# payload-externalPCB-version2-modif2.net
KiCad netlist of a schematic drawn in EAGLE
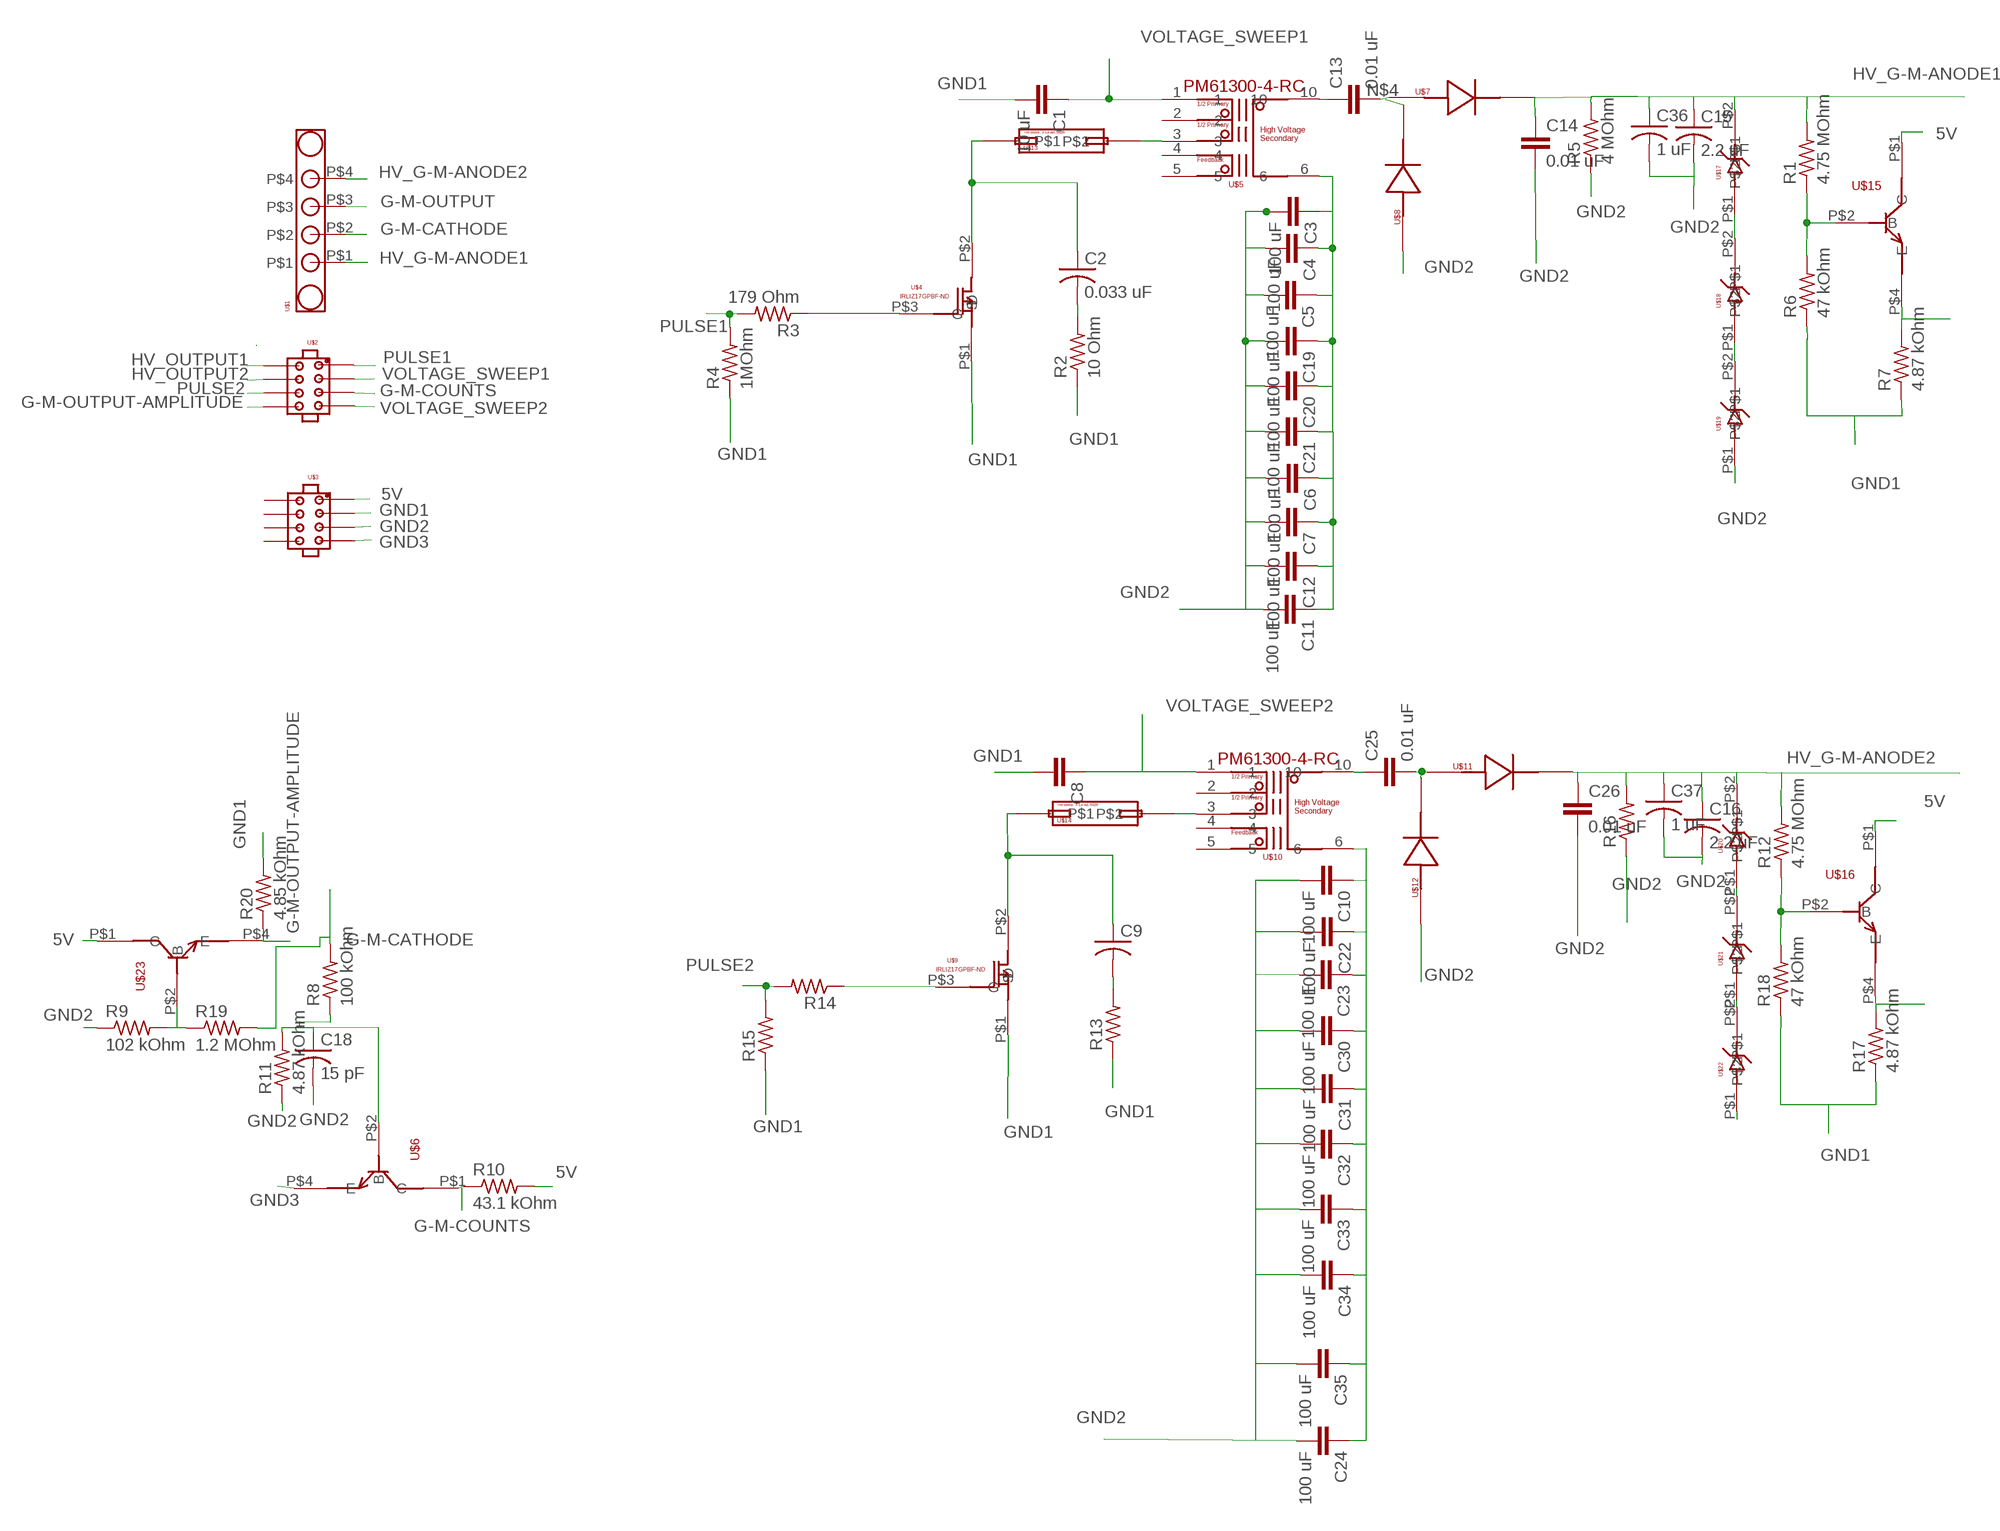
[diagram p0: schematic, sheet 1]

(export (version "E")
  (design (tool "Eeschema 10.0.6"))
  (components
    (comp (ref "C1")
      (value "10 uF")
      (footprint "eagle-import:C1210")
      (libsource (lib "eagle-import") (part "C-EUC1210"))
    )
    (comp (ref "C2")
      (value "0.033 uF")
      (footprint "eagle-import:C0805")
      (libsource (lib "eagle-import") (part "C-USC0805"))
    )
    (comp (ref "C3")
      (value "100 uF")
      (footprint "eagle-import:C1210")
      (libsource (lib "eagle-import") (part "C-EUC1210"))
    )
    (comp (ref "C4")
      (value "100 uF")
      (footprint "eagle-import:C1210")
      (libsource (lib "eagle-import") (part "C-EUC1210"))
    )
    (comp (ref "C5")
      (value "100 uF")
      (footprint "eagle-import:C1210")
      (libsource (lib "eagle-import") (part "C-EUC1210"))
    )
    (comp (ref "C6")
      (value "100 uF")
      (footprint "eagle-import:C1210")
      (libsource (lib "eagle-import") (part "C-EUC1210"))
    )
    (comp (ref "C7")
      (value "100 uF")
      (footprint "eagle-import:C1210")
      (libsource (lib "eagle-import") (part "C-EUC1210"))
    )
    (comp (ref "C8")
      (value "C-EUC1210")
      (footprint "eagle-import:C1210")
      (libsource (lib "eagle-import") (part "C-EUC1210"))
    )
    (comp (ref "C9")
      (value "C-USC0805")
      (footprint "eagle-import:C0805")
      (libsource (lib "eagle-import") (part "C-USC0805"))
    )
    (comp (ref "C10")
      (value "100 uF")
      (footprint "eagle-import:C1210")
      (libsource (lib "eagle-import") (part "C-EUC1210"))
    )
    (comp (ref "C11")
      (value "100 uF")
      (footprint "eagle-import:C1210")
      (libsource (lib "eagle-import") (part "C-EUC1210"))
    )
    (comp (ref "C12")
      (value "100 uF")
      (footprint "eagle-import:C1210")
      (libsource (lib "eagle-import") (part "C-EUC1210"))
    )
    (comp (ref "C13")
      (value "0.01 uF")
      (footprint "eagle-import:C1206")
      (libsource (lib "eagle-import") (part "C-EUC1206"))
    )
    (comp (ref "C14")
      (value "0.01 uF")
      (footprint "eagle-import:C1206")
      (libsource (lib "eagle-import") (part "C-EUC1206"))
    )
    (comp (ref "C15")
      (value "2.2 uF")
      (footprint "eagle-import:C2220K")
      (libsource (lib "eagle-import") (part "C-USC2220K"))
    )
    (comp (ref "C16")
      (value "2.2 uF")
      (footprint "eagle-import:C2220K")
      (libsource (lib "eagle-import") (part "C-USC2220K"))
    )
    (comp (ref "C18")
      (value "15 pF")
      (footprint "eagle-import:C0805")
      (libsource (lib "eagle-import") (part "C-USC0805"))
    )
    (comp (ref "C19")
      (value "100 uF")
      (footprint "eagle-import:C1210")
      (libsource (lib "eagle-import") (part "C-EUC1210"))
    )
    (comp (ref "C20")
      (value "100 uF")
      (footprint "eagle-import:C1210")
      (libsource (lib "eagle-import") (part "C-EUC1210"))
    )
    (comp (ref "C21")
      (value "100 uF")
      (footprint "eagle-import:C1210")
      (libsource (lib "eagle-import") (part "C-EUC1210"))
    )
    (comp (ref "C22")
      (value "100 uF")
      (footprint "eagle-import:C1210")
      (libsource (lib "eagle-import") (part "C-EUC1210"))
    )
    (comp (ref "C23")
      (value "100 uF")
      (footprint "eagle-import:C1210")
      (libsource (lib "eagle-import") (part "C-EUC1210"))
    )
    (comp (ref "C24")
      (value "100 uF")
      (footprint "eagle-import:C1210")
      (libsource (lib "eagle-import") (part "C-EUC1210"))
    )
    (comp (ref "C25")
      (value "0.01 uF")
      (footprint "eagle-import:C1206")
      (libsource (lib "eagle-import") (part "C-EUC1206"))
    )
    (comp (ref "C26")
      (value "0.01 uF")
      (footprint "eagle-import:C1206")
      (libsource (lib "eagle-import") (part "C-EUC1206"))
    )
    (comp (ref "C30")
      (value "100 uF")
      (footprint "eagle-import:C1210")
      (libsource (lib "eagle-import") (part "C-EUC1210"))
    )
    (comp (ref "C31")
      (value "100 uF")
      (footprint "eagle-import:C1210")
      (libsource (lib "eagle-import") (part "C-EUC1210"))
    )
    (comp (ref "C32")
      (value "100 uF")
      (footprint "eagle-import:C1210")
      (libsource (lib "eagle-import") (part "C-EUC1210"))
    )
    (comp (ref "C33")
      (value "100 uF")
      (footprint "eagle-import:C1210")
      (libsource (lib "eagle-import") (part "C-EUC1210"))
    )
    (comp (ref "C34")
      (value "100 uF")
      (footprint "eagle-import:C1210")
      (libsource (lib "eagle-import") (part "C-EUC1210"))
    )
    (comp (ref "C35")
      (value "100 uF")
      (footprint "eagle-import:C1210")
      (libsource (lib "eagle-import") (part "C-EUC1210"))
    )
    (comp (ref "C36")
      (value "1 uF")
      (footprint "eagle-import:C2220K")
      (libsource (lib "eagle-import") (part "C-USC2220K"))
    )
    (comp (ref "C37")
      (value "1 uF")
      (footprint "eagle-import:C2220K")
      (libsource (lib "eagle-import") (part "C-USC2220K"))
    )
    (comp (ref "R1")
      (value "4.75 MOhm")
      (footprint "eagle-import:R1206")
      (libsource (lib "eagle-import") (part "R-US_R1206"))
    )
    (comp (ref "R2")
      (value "10 Ohm")
      (footprint "eagle-import:R2010")
      (libsource (lib "eagle-import") (part "R-US_R2010"))
    )
    (comp (ref "R3")
      (value "179 Ohm")
      (footprint "eagle-import:R2010")
      (libsource (lib "eagle-import") (part "R-US_R2010"))
    )
    (comp (ref "R4")
      (value "1MOhm")
      (footprint "eagle-import:R2010")
      (libsource (lib "eagle-import") (part "R-US_R2010"))
    )
    (comp (ref "R5")
      (value "4 MOhm")
      (footprint "eagle-import:R2010")
      (libsource (lib "eagle-import") (part "R-US_R2010"))
    )
    (comp (ref "R6")
      (value "47 kOhm")
      (footprint "eagle-import:R1210")
      (libsource (lib "eagle-import") (part "R-US_R1210"))
    )
    (comp (ref "R7")
      (value "4.87 kOhm")
      (footprint "eagle-import:R2010")
      (libsource (lib "eagle-import") (part "R-US_R2010"))
    )
    (comp (ref "R8")
      (value "100 kOhm")
      (footprint "eagle-import:R2010")
      (libsource (lib "eagle-import") (part "R-US_R2010"))
    )
    (comp (ref "R9")
      (value "102 kOhm")
      (footprint "eagle-import:R1206")
      (libsource (lib "eagle-import") (part "R-US_R1206"))
    )
    (comp (ref "R10")
      (value "43.1 kOhm")
      (footprint "eagle-import:R2010")
      (libsource (lib "eagle-import") (part "R-US_R2010"))
    )
    (comp (ref "R11")
      (value "4.87 kOhm")
      (footprint "eagle-import:R1210")
      (libsource (lib "eagle-import") (part "R-US_R1210"))
    )
    (comp (ref "R12")
      (value "4.75 MOhm")
      (footprint "eagle-import:R1206")
      (libsource (lib "eagle-import") (part "R-US_R1206"))
    )
    (comp (ref "R13")
      (value "R-US_R2010")
      (footprint "eagle-import:R2010")
      (libsource (lib "eagle-import") (part "R-US_R2010"))
    )
    (comp (ref "R14")
      (value "R-US_R2010")
      (footprint "eagle-import:R2010")
      (libsource (lib "eagle-import") (part "R-US_R2010"))
    )
    (comp (ref "R15")
      (value "R-US_R2010")
      (footprint "eagle-import:R2010")
      (libsource (lib "eagle-import") (part "R-US_R2010"))
    )
    (comp (ref "R16")
      (value "R-US_R2010")
      (footprint "eagle-import:R2010")
      (libsource (lib "eagle-import") (part "R-US_R2010"))
    )
    (comp (ref "R17")
      (value "4.87 kOhm")
      (footprint "eagle-import:R2010")
      (libsource (lib "eagle-import") (part "R-US_R2010"))
    )
    (comp (ref "R18")
      (value "47 kOhm")
      (footprint "eagle-import:R1210")
      (libsource (lib "eagle-import") (part "R-US_R1210"))
    )
    (comp (ref "R19")
      (value "1.2 MOhm")
      (footprint "eagle-import:R1206")
      (libsource (lib "eagle-import") (part "R-US_R1206"))
    )
    (comp (ref "R20")
      (value "4.85 kOhm")
      (footprint "eagle-import:R2010")
      (libsource (lib "eagle-import") (part "R-US_R2010"))
    )
    (comp (ref "U$1")
      (value "M80-5000000M2-04-331-00-000")
      (footprint "eagle-import:M80-5000000M2-04-331-00-000")
      (libsource (lib "eagle-import") (part "M80-5000000M2-04-331-00-000"))
    )
    (comp (ref "U$2")
      (value "M80-8670805")
      (footprint "eagle-import:M80-8670805")
      (libsource (lib "eagle-import") (part "M80-8670805"))
    )
    (comp (ref "U$3")
      (value "M80-8670805")
      (footprint "eagle-import:M80-8670805")
      (libsource (lib "eagle-import") (part "M80-8670805"))
    )
    (comp (ref "U$4")
      (value "IRLIZ14GPBF-ND-SCHEMATICS")
      (footprint "eagle-import:TO-220FULLPAK-IRLIZ14GPBF-ND")
      (libsource (lib "eagle-import") (part "IRLIZ14GPBF-ND-SCHEMATICS"))
    )
    (comp (ref "U$5")
      (value "PM61300-4-RC")
      (footprint "eagle-import:PM61300-4-RC")
      (libsource (lib "eagle-import") (part "PM61300-4-RC"))
    )
    (comp (ref "U$6")
      (value "PZT3904-SOT223-SCHEMATICS")
      (footprint "eagle-import:SOT223-PZT3904")
      (libsource (lib "eagle-import") (part "PZT3904-SOT223-SCHEMATICS"))
    )
    (comp (ref "U$7")
      (value "S1J-SCHEMATICS")
      (footprint "eagle-import:DO-214AC-S1J")
      (libsource (lib "eagle-import") (part "S1J-SCHEMATICS"))
    )
    (comp (ref "U$8")
      (value "S1J-SCHEMATICS")
      (footprint "eagle-import:DO-214AC-S1J")
      (libsource (lib "eagle-import") (part "S1J-SCHEMATICS"))
    )
    (comp (ref "U$9")
      (value "IRLIZ14GPBF-ND-SCHEMATICS")
      (footprint "eagle-import:TO-220FULLPAK-IRLIZ14GPBF-ND")
      (libsource (lib "eagle-import") (part "IRLIZ14GPBF-ND-SCHEMATICS"))
    )
    (comp (ref "U$10")
      (value "PM61300-4-RC")
      (footprint "eagle-import:PM61300-4-RC")
      (libsource (lib "eagle-import") (part "PM61300-4-RC"))
    )
    (comp (ref "U$11")
      (value "S1J-SCHEMATICS")
      (footprint "eagle-import:DO-214AC-S1J")
      (libsource (lib "eagle-import") (part "S1J-SCHEMATICS"))
    )
    (comp (ref "U$12")
      (value "S1J-SCHEMATICS")
      (footprint "eagle-import:DO-214AC-S1J")
      (libsource (lib "eagle-import") (part "S1J-SCHEMATICS"))
    )
    (comp (ref "U$13")
      (value "RESISTOR-J-LEAD-5W")
      (footprint "eagle-import:PACKAGE-13573-J-LEAD")
      (libsource (lib "eagle-import") (part "RESISTOR-J-LEAD-5W"))
    )
    (comp (ref "U$14")
      (value "RESISTOR-J-LEAD-5W")
      (footprint "eagle-import:PACKAGE-13573-J-LEAD")
      (libsource (lib "eagle-import") (part "RESISTOR-J-LEAD-5W"))
    )
    (comp (ref "U$15")
      (value "PZT3904-SOT223-SCHEMATICS")
      (footprint "eagle-import:SOT223-PZT3904")
      (libsource (lib "eagle-import") (part "PZT3904-SOT223-SCHEMATICS"))
    )
    (comp (ref "U$16")
      (value "PZT3904-SOT223-SCHEMATICS")
      (footprint "eagle-import:SOT223-PZT3904")
      (libsource (lib "eagle-import") (part "PZT3904-SOT223-SCHEMATICS"))
    )
    (comp (ref "U$17")
      (value "SMBJ5388B-ZENER-DIODE-200V")
      (footprint "eagle-import:DO-214AA-SMBJ5388B-ZENER")
      (libsource (lib "eagle-import") (part "SMBJ5388B-ZENER-DIODE-200V"))
    )
    (comp (ref "U$18")
      (value "SMBJ5388B-ZENER-DIODE-200V")
      (footprint "eagle-import:DO-214AA-SMBJ5388B-ZENER")
      (libsource (lib "eagle-import") (part "SMBJ5388B-ZENER-DIODE-200V"))
    )
    (comp (ref "U$19")
      (value "SMBJ5388B-ZENER-DIODE-200V")
      (footprint "eagle-import:DO-214AA-SMBJ5388B-ZENER")
      (libsource (lib "eagle-import") (part "SMBJ5388B-ZENER-DIODE-200V"))
    )
    (comp (ref "U$20")
      (value "SMBJ5388B-ZENER-DIODE-200V")
      (footprint "eagle-import:DO-214AA-SMBJ5388B-ZENER")
      (libsource (lib "eagle-import") (part "SMBJ5388B-ZENER-DIODE-200V"))
    )
    (comp (ref "U$21")
      (value "SMBJ5388B-ZENER-DIODE-200V")
      (footprint "eagle-import:DO-214AA-SMBJ5388B-ZENER")
      (libsource (lib "eagle-import") (part "SMBJ5388B-ZENER-DIODE-200V"))
    )
    (comp (ref "U$22")
      (value "SMBJ5388B-ZENER-DIODE-200V")
      (footprint "eagle-import:DO-214AA-SMBJ5388B-ZENER")
      (libsource (lib "eagle-import") (part "SMBJ5388B-ZENER-DIODE-200V"))
    )
    (comp (ref "U$23")
      (value "PZT3904-SOT223-SCHEMATICS")
      (footprint "eagle-import:SOT223-PZT3904")
      (libsource (lib "eagle-import") (part "PZT3904-SOT223-SCHEMATICS"))
    )
  )
  (nets
    (net (code "1") (name "/5V") (class "Default")
      (node (ref "R10") (pin "2") (pinfunction "2_2") (pintype "passive"))
      (node (ref "U$15") (pin "P$1") (pinfunction "C_P$1") (pintype "bidirectional"))
      (node (ref "U$16") (pin "P$1") (pinfunction "C_P$1") (pintype "bidirectional"))
      (node (ref "U$23") (pin "P$1") (pinfunction "C_P$1") (pintype "bidirectional"))
      (node (ref "U$3") (pin "P$1") (pinfunction "P$1_P$1") (pintype "bidirectional"))
    )
    (net (code "2") (name "/G-M-CATHODE") (class "Default")
      (node (ref "R19") (pin "2") (pinfunction "2_2") (pintype "passive"))
      (node (ref "R8") (pin "2") (pinfunction "2_2") (pintype "passive"))
      (node (ref "U$1") (pin "P$2") (pinfunction "P$2_P$2") (pintype "bidirectional"))
    )
    (net (code "3") (name "/G-M-COUNTS") (class "Default")
      (node (ref "R10") (pin "1") (pinfunction "1_1") (pintype "passive"))
      (node (ref "U$2") (pin "P$3") (pinfunction "P$3_P$3") (pintype "bidirectional"))
      (node (ref "U$6") (pin "P$1") (pinfunction "C_P$1") (pintype "bidirectional"))
    )
    (net (code "4") (name "/G-M-OUTPUT") (class "Default")
      (node (ref "U$1") (pin "P$3") (pinfunction "P$3_P$3") (pintype "bidirectional"))
    )
    (net (code "5") (name "/G-M-OUTPUT-AMPLITUDE") (class "Default")
      (node (ref "R20") (pin "1") (pinfunction "1_1") (pintype "passive"))
      (node (ref "U$2") (pin "P$8") (pinfunction "P$8_P$8") (pintype "bidirectional"))
      (node (ref "U$23") (pin "P$4") (pinfunction "E_P$4") (pintype "bidirectional"))
    )
    (net (code "6") (name "/GND1") (class "Default")
      (node (ref "C1") (pin "2") (pinfunction "2_2") (pintype "passive"))
      (node (ref "C8") (pin "2") (pinfunction "2_2") (pintype "passive"))
      (node (ref "R13") (pin "1") (pinfunction "1_1") (pintype "passive"))
      (node (ref "R15") (pin "1") (pinfunction "1_1") (pintype "passive"))
      (node (ref "R17") (pin "1") (pinfunction "1_1") (pintype "passive"))
      (node (ref "R18") (pin "1") (pinfunction "1_1") (pintype "passive"))
      (node (ref "R2") (pin "1") (pinfunction "1_1") (pintype "passive"))
      (node (ref "R20") (pin "2") (pinfunction "2_2") (pintype "passive"))
      (node (ref "R4") (pin "1") (pinfunction "1_1") (pintype "passive"))
      (node (ref "R6") (pin "1") (pinfunction "1_1") (pintype "passive"))
      (node (ref "R7") (pin "1") (pinfunction "1_1") (pintype "passive"))
      (node (ref "U$3") (pin "P$2") (pinfunction "P$2_P$2") (pintype "bidirectional"))
      (node (ref "U$4") (pin "P$1") (pinfunction "S_P$1") (pintype "bidirectional"))
      (node (ref "U$9") (pin "P$1") (pinfunction "S_P$1") (pintype "bidirectional"))
    )
    (net (code "7") (name "/GND2") (class "Default")
      (node (ref "C10") (pin "2") (pinfunction "2_2") (pintype "passive"))
      (node (ref "C11") (pin "2") (pinfunction "2_2") (pintype "passive"))
      (node (ref "C12") (pin "2") (pinfunction "2_2") (pintype "passive"))
      (node (ref "C14") (pin "2") (pinfunction "2_2") (pintype "passive"))
      (node (ref "C15") (pin "2") (pinfunction "2_2") (pintype "passive"))
      (node (ref "C16") (pin "2") (pinfunction "2_2") (pintype "passive"))
      (node (ref "C18") (pin "2") (pinfunction "2_2") (pintype "passive"))
      (node (ref "C19") (pin "2") (pinfunction "2_2") (pintype "passive"))
      (node (ref "C20") (pin "2") (pinfunction "2_2") (pintype "passive"))
      (node (ref "C21") (pin "2") (pinfunction "2_2") (pintype "passive"))
      (node (ref "C22") (pin "2") (pinfunction "2_2") (pintype "passive"))
      (node (ref "C23") (pin "2") (pinfunction "2_2") (pintype "passive"))
      (node (ref "C24") (pin "2") (pinfunction "2_2") (pintype "passive"))
      (node (ref "C26") (pin "2") (pinfunction "2_2") (pintype "passive"))
      (node (ref "C3") (pin "2") (pinfunction "2_2") (pintype "passive"))
      (node (ref "C30") (pin "2") (pinfunction "2_2") (pintype "passive"))
      (node (ref "C31") (pin "2") (pinfunction "2_2") (pintype "passive"))
      (node (ref "C32") (pin "2") (pinfunction "2_2") (pintype "passive"))
      (node (ref "C33") (pin "2") (pinfunction "2_2") (pintype "passive"))
      (node (ref "C34") (pin "2") (pinfunction "2_2") (pintype "passive"))
      (node (ref "C35") (pin "2") (pinfunction "2_2") (pintype "passive"))
      (node (ref "C36") (pin "2") (pinfunction "2_2") (pintype "passive"))
      (node (ref "C37") (pin "2") (pinfunction "2_2") (pintype "passive"))
      (node (ref "C4") (pin "2") (pinfunction "2_2") (pintype "passive"))
      (node (ref "C5") (pin "2") (pinfunction "2_2") (pintype "passive"))
      (node (ref "C6") (pin "2") (pinfunction "2_2") (pintype "passive"))
      (node (ref "C7") (pin "2") (pinfunction "2_2") (pintype "passive"))
      (node (ref "R11") (pin "1") (pinfunction "1_1") (pintype "passive"))
      (node (ref "R16") (pin "1") (pinfunction "1_1") (pintype "passive"))
      (node (ref "R5") (pin "1") (pinfunction "1_1") (pintype "passive"))
      (node (ref "R9") (pin "1") (pinfunction "1_1") (pintype "passive"))
      (node (ref "U$12") (pin "P$1") (pinfunction "A_P$1") (pintype "bidirectional"))
      (node (ref "U$19") (pin "P$1") (pinfunction "P$1_P$1") (pintype "bidirectional"))
      (node (ref "U$22") (pin "P$1") (pinfunction "P$1_P$1") (pintype "bidirectional"))
      (node (ref "U$3") (pin "P$3") (pinfunction "P$3_P$3") (pintype "bidirectional"))
      (node (ref "U$8") (pin "P$1") (pinfunction "A_P$1") (pintype "bidirectional"))
    )
    (net (code "8") (name "/GND3") (class "Default")
      (node (ref "U$3") (pin "P$4") (pinfunction "P$4_P$4") (pintype "bidirectional"))
      (node (ref "U$6") (pin "P$4") (pinfunction "E_P$4") (pintype "bidirectional"))
    )
    (net (code "9") (name "/HV_G-M-ANODE1") (class "Default")
      (node (ref "C14") (pin "1") (pinfunction "1_1") (pintype "passive"))
      (node (ref "C15") (pin "1") (pinfunction "1_1") (pintype "passive"))
      (node (ref "C36") (pin "1") (pinfunction "1_1") (pintype "passive"))
      (node (ref "R1") (pin "2") (pinfunction "2_2") (pintype "passive"))
      (node (ref "R5") (pin "2") (pinfunction "2_2") (pintype "passive"))
      (node (ref "U$1") (pin "P$1") (pinfunction "P$1_P$1") (pintype "bidirectional"))
      (node (ref "U$17") (pin "P$2") (pinfunction "P$2_P$2") (pintype "bidirectional"))
      (node (ref "U$7") (pin "P$2") (pinfunction "C_P$2") (pintype "bidirectional"))
    )
    (net (code "10") (name "/HV_G-M-ANODE2") (class "Default")
      (node (ref "C16") (pin "1") (pinfunction "1_1") (pintype "passive"))
      (node (ref "C26") (pin "1") (pinfunction "1_1") (pintype "passive"))
      (node (ref "C37") (pin "1") (pinfunction "1_1") (pintype "passive"))
      (node (ref "R12") (pin "2") (pinfunction "2_2") (pintype "passive"))
      (node (ref "R16") (pin "2") (pinfunction "2_2") (pintype "passive"))
      (node (ref "U$1") (pin "P$4") (pinfunction "P$4_P$4") (pintype "bidirectional"))
      (node (ref "U$11") (pin "P$2") (pinfunction "C_P$2") (pintype "bidirectional"))
      (node (ref "U$20") (pin "P$2") (pinfunction "P$2_P$2") (pintype "bidirectional"))
    )
    (net (code "11") (name "/HV_OUTPUT1") (class "Default")
      (node (ref "R7") (pin "2") (pinfunction "2_2") (pintype "passive"))
      (node (ref "U$15") (pin "P$4") (pinfunction "E_P$4") (pintype "bidirectional"))
      (node (ref "U$2") (pin "P$5") (pinfunction "P$5_P$5") (pintype "bidirectional"))
    )
    (net (code "12") (name "/HV_OUTPUT2") (class "Default")
      (node (ref "R17") (pin "2") (pinfunction "2_2") (pintype "passive"))
      (node (ref "U$16") (pin "P$4") (pinfunction "E_P$4") (pintype "bidirectional"))
      (node (ref "U$2") (pin "P$6") (pinfunction "P$6_P$6") (pintype "bidirectional"))
    )
    (net (code "13") (name "/N$4") (class "Default")
      (node (ref "C13") (pin "2") (pinfunction "2_2") (pintype "passive"))
      (node (ref "U$7") (pin "P$1") (pinfunction "A_P$1") (pintype "bidirectional"))
      (node (ref "U$8") (pin "P$2") (pinfunction "C_P$2") (pintype "bidirectional"))
    )
    (net (code "14") (name "/N$6") (class "Default")
      (node (ref "C11") (pin "1") (pinfunction "1_1") (pintype "passive"))
      (node (ref "C12") (pin "1") (pinfunction "1_1") (pintype "passive"))
      (node (ref "C19") (pin "1") (pinfunction "1_1") (pintype "passive"))
      (node (ref "C20") (pin "1") (pinfunction "1_1") (pintype "passive"))
      (node (ref "C21") (pin "1") (pinfunction "1_1") (pintype "passive"))
      (node (ref "C3") (pin "1") (pinfunction "1_1") (pintype "passive"))
      (node (ref "C4") (pin "1") (pinfunction "1_1") (pintype "passive"))
      (node (ref "C5") (pin "1") (pinfunction "1_1") (pintype "passive"))
      (node (ref "C6") (pin "1") (pinfunction "1_1") (pintype "passive"))
      (node (ref "C7") (pin "1") (pinfunction "1_1") (pintype "passive"))
      (node (ref "U$5") (pin "6") (pinfunction "6_6") (pintype "bidirectional"))
    )
    (net (code "15") (name "/N$9") (class "Default")
      (node (ref "C10") (pin "1") (pinfunction "1_1") (pintype "passive"))
      (node (ref "C22") (pin "1") (pinfunction "1_1") (pintype "passive"))
      (node (ref "C23") (pin "1") (pinfunction "1_1") (pintype "passive"))
      (node (ref "C24") (pin "1") (pinfunction "1_1") (pintype "passive"))
      (node (ref "C30") (pin "1") (pinfunction "1_1") (pintype "passive"))
      (node (ref "C31") (pin "1") (pinfunction "1_1") (pintype "passive"))
      (node (ref "C32") (pin "1") (pinfunction "1_1") (pintype "passive"))
      (node (ref "C33") (pin "1") (pinfunction "1_1") (pintype "passive"))
      (node (ref "C34") (pin "1") (pinfunction "1_1") (pintype "passive"))
      (node (ref "C35") (pin "1") (pinfunction "1_1") (pintype "passive"))
      (node (ref "U$10") (pin "6") (pinfunction "6_6") (pintype "bidirectional"))
    )
    (net (code "16") (name "/N$26") (class "Default")
      (node (ref "C9") (pin "1") (pinfunction "1_1") (pintype "passive"))
      (node (ref "U$14") (pin "P$1") (pinfunction "P$1_P$1") (pintype "bidirectional"))
      (node (ref "U$9") (pin "P$2") (pinfunction "D_P$2") (pintype "bidirectional"))
    )
    (net (code "17") (name "/N$46") (class "Default")
      (node (ref "C18") (pin "1") (pinfunction "1_1") (pintype "passive"))
      (node (ref "R11") (pin "2") (pinfunction "2_2") (pintype "passive"))
      (node (ref "R8") (pin "1") (pinfunction "1_1") (pintype "passive"))
      (node (ref "U$6") (pin "P$2") (pinfunction "B_P$2") (pintype "bidirectional"))
    )
    (net (code "18") (name "/N$47") (class "Default")
      (node (ref "R19") (pin "1") (pinfunction "1_1") (pintype "passive"))
      (node (ref "R9") (pin "2") (pinfunction "2_2") (pintype "passive"))
      (node (ref "U$23") (pin "P$2") (pinfunction "B_P$2") (pintype "bidirectional"))
    )
    (net (code "19") (name "/PULSE1") (class "Default")
      (node (ref "R3") (pin "2") (pinfunction "2_2") (pintype "passive"))
      (node (ref "R4") (pin "2") (pinfunction "2_2") (pintype "passive"))
      (node (ref "U$2") (pin "P$1") (pinfunction "P$1_P$1") (pintype "bidirectional"))
    )
    (net (code "20") (name "/PULSE2") (class "Default")
      (node (ref "R14") (pin "2") (pinfunction "2_2") (pintype "passive"))
      (node (ref "R15") (pin "2") (pinfunction "2_2") (pintype "passive"))
      (node (ref "U$2") (pin "P$7") (pinfunction "P$7_P$7") (pintype "bidirectional"))
    )
    (net (code "21") (name "/VOLTAGE_SWEEP1") (class "Default")
      (node (ref "C1") (pin "1") (pinfunction "1_1") (pintype "passive"))
      (node (ref "U$2") (pin "P$2") (pinfunction "P$2_P$2") (pintype "bidirectional"))
      (node (ref "U$5") (pin "1") (pinfunction "1_1") (pintype "bidirectional"))
    )
    (net (code "22") (name "/VOLTAGE_SWEEP2") (class "Default")
      (node (ref "C8") (pin "1") (pinfunction "1_1") (pintype "passive"))
      (node (ref "U$10") (pin "1") (pinfunction "1_1") (pintype "bidirectional"))
      (node (ref "U$2") (pin "P$4") (pinfunction "P$4_P$4") (pintype "bidirectional"))
    )
    (net (code "23") (name "Net-(C2-Pad2)") (class "Default")
      (node (ref "C2") (pin "2") (pinfunction "2_2") (pintype "passive"))
      (node (ref "R2") (pin "2") (pinfunction "2_2") (pintype "passive"))
    )
    (net (code "24") (name "Net-(C9-Pad2)") (class "Default")
      (node (ref "C9") (pin "2") (pinfunction "2_2") (pintype "passive"))
      (node (ref "R13") (pin "2") (pinfunction "2_2") (pintype "passive"))
    )
    (net (code "25") (name "Net-(C13-Pad1)") (class "Default")
      (node (ref "C13") (pin "1") (pinfunction "1_1") (pintype "passive"))
      (node (ref "U$5") (pin "10") (pinfunction "10_10") (pintype "bidirectional"))
    )
    (net (code "26") (name "Net-(C25-Pad1)") (class "Default")
      (node (ref "C25") (pin "1") (pinfunction "1_1") (pintype "passive"))
      (node (ref "U$10") (pin "10") (pinfunction "10_10") (pintype "bidirectional"))
    )
    (net (code "27") (name "Net-(U$4-D)") (class "Default")
      (node (ref "C2") (pin "1") (pinfunction "1_1") (pintype "passive"))
      (node (ref "U$13") (pin "P$1") (pinfunction "P$1_P$1") (pintype "bidirectional"))
      (node (ref "U$4") (pin "P$2") (pinfunction "D_P$2") (pintype "bidirectional"))
    )
    (net (code "28") (name "Net-(U$4-G)") (class "Default")
      (node (ref "R3") (pin "1") (pinfunction "1_1") (pintype "passive"))
      (node (ref "U$4") (pin "P$3") (pinfunction "G_P$3") (pintype "bidirectional"))
    )
    (net (code "29") (name "Net-(U$9-G)") (class "Default")
      (node (ref "R14") (pin "1") (pinfunction "1_1") (pintype "passive"))
      (node (ref "U$9") (pin "P$3") (pinfunction "G_P$3") (pintype "bidirectional"))
    )
    (net (code "30") (name "Net-(U$10-Pad3)") (class "Default")
      (node (ref "U$10") (pin "3") (pinfunction "3_3") (pintype "bidirectional"))
      (node (ref "U$14") (pin "P$2") (pinfunction "P$2_P$2") (pintype "bidirectional"))
    )
    (net (code "31") (name "Net-(U$11-A)") (class "Default")
      (node (ref "C25") (pin "2") (pinfunction "2_2") (pintype "passive"))
      (node (ref "U$11") (pin "P$1") (pinfunction "A_P$1") (pintype "bidirectional"))
      (node (ref "U$12") (pin "P$2") (pinfunction "C_P$2") (pintype "bidirectional"))
    )
    (net (code "32") (name "Net-(U$13-PadP$2)") (class "Default")
      (node (ref "U$13") (pin "P$2") (pinfunction "P$2_P$2") (pintype "bidirectional"))
      (node (ref "U$5") (pin "3") (pinfunction "3_3") (pintype "bidirectional"))
    )
    (net (code "33") (name "Net-(U$15-B)") (class "Default")
      (node (ref "R1") (pin "1") (pinfunction "1_1") (pintype "passive"))
      (node (ref "R6") (pin "2") (pinfunction "2_2") (pintype "passive"))
      (node (ref "U$15") (pin "P$2") (pinfunction "B_P$2") (pintype "bidirectional"))
    )
    (net (code "34") (name "Net-(U$16-B)") (class "Default")
      (node (ref "R12") (pin "1") (pinfunction "1_1") (pintype "passive"))
      (node (ref "R18") (pin "2") (pinfunction "2_2") (pintype "passive"))
      (node (ref "U$16") (pin "P$2") (pinfunction "B_P$2") (pintype "bidirectional"))
    )
    (net (code "35") (name "Net-(U$17-PadP$1)") (class "Default")
      (node (ref "U$17") (pin "P$1") (pinfunction "P$1_P$1") (pintype "bidirectional"))
      (node (ref "U$18") (pin "P$2") (pinfunction "P$2_P$2") (pintype "bidirectional"))
    )
    (net (code "36") (name "Net-(U$18-PadP$1)") (class "Default")
      (node (ref "U$18") (pin "P$1") (pinfunction "P$1_P$1") (pintype "bidirectional"))
      (node (ref "U$19") (pin "P$2") (pinfunction "P$2_P$2") (pintype "bidirectional"))
    )
    (net (code "37") (name "Net-(U$20-PadP$1)") (class "Default")
      (node (ref "U$20") (pin "P$1") (pinfunction "P$1_P$1") (pintype "bidirectional"))
      (node (ref "U$21") (pin "P$2") (pinfunction "P$2_P$2") (pintype "bidirectional"))
    )
    (net (code "38") (name "Net-(U$21-PadP$1)") (class "Default")
      (node (ref "U$21") (pin "P$1") (pinfunction "P$1_P$1") (pintype "bidirectional"))
      (node (ref "U$22") (pin "P$2") (pinfunction "P$2_P$2") (pintype "bidirectional"))
    )
    (net (code "39") (name "unconnected-(U$3-PadP$5)") (class "Default")
      (node (ref "U$3") (pin "P$5") (pinfunction "P$5_P$5") (pintype "bidirectional"))
    )
    (net (code "40") (name "unconnected-(U$3-PadP$6)") (class "Default")
      (node (ref "U$3") (pin "P$6") (pinfunction "P$6_P$6") (pintype "bidirectional"))
    )
    (net (code "41") (name "unconnected-(U$3-PadP$7)") (class "Default")
      (node (ref "U$3") (pin "P$7") (pinfunction "P$7_P$7") (pintype "bidirectional"))
    )
    (net (code "42") (name "unconnected-(U$3-PadP$8)") (class "Default")
      (node (ref "U$3") (pin "P$8") (pinfunction "P$8_P$8") (pintype "bidirectional"))
    )
    (net (code "43") (name "unconnected-(U$5-Pad2)") (class "Default")
      (node (ref "U$5") (pin "2") (pinfunction "2_2") (pintype "bidirectional"))
    )
    (net (code "44") (name "unconnected-(U$5-Pad4)") (class "Default")
      (node (ref "U$5") (pin "4") (pinfunction "4_4") (pintype "bidirectional"))
    )
    (net (code "45") (name "unconnected-(U$5-Pad5)") (class "Default")
      (node (ref "U$5") (pin "5") (pinfunction "5_5") (pintype "bidirectional"))
    )
    (net (code "46") (name "unconnected-(U$10-Pad2)") (class "Default")
      (node (ref "U$10") (pin "2") (pinfunction "2_2") (pintype "bidirectional"))
    )
    (net (code "47") (name "unconnected-(U$10-Pad4)") (class "Default")
      (node (ref "U$10") (pin "4") (pinfunction "4_4") (pintype "bidirectional"))
    )
    (net (code "48") (name "unconnected-(U$10-Pad5)") (class "Default")
      (node (ref "U$10") (pin "5") (pinfunction "5_5") (pintype "bidirectional"))
    )
  )
)
